# W023.net
KiCad netlist of a schematic drawn in EAGLE
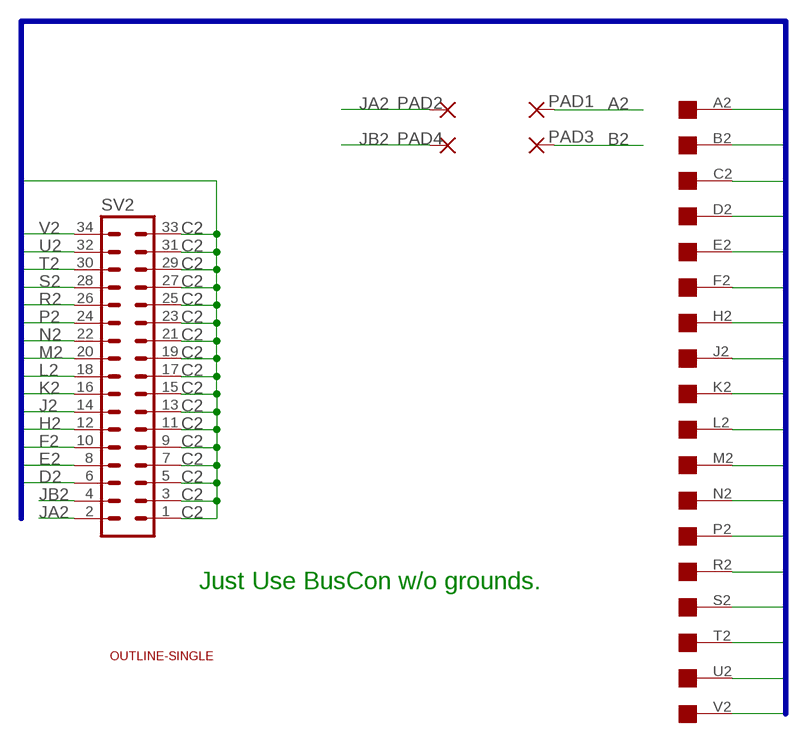
[diagram p0: schematic, sheet 1]

(export (version "E")
  (design (tool "Eeschema 10.0.6"))
  (components
    (comp (ref "PAD1")
      (value "1,6/0,8")
      (footprint "eagle-import:1,6_0,8")
      (libsource (lib "eagle-import") (part "1,6/0,8"))
    )
    (comp (ref "PAD2")
      (value "1,6/0,8")
      (footprint "eagle-import:1,6_0,8")
      (libsource (lib "eagle-import") (part "1,6/0,8"))
    )
    (comp (ref "PAD3")
      (value "1,6/0,8")
      (footprint "eagle-import:1,6_0,8")
      (libsource (lib "eagle-import") (part "1,6/0,8"))
    )
    (comp (ref "PAD4")
      (value "1,6/0,8")
      (footprint "eagle-import:1,6_0,8")
      (libsource (lib "eagle-import") (part "1,6/0,8"))
    )
    (comp (ref "SV2")
      (value "MA17-2")
      (footprint "eagle-import:MA17-2")
      (libsource (lib "eagle-import") (part "MA17-2"))
    )
    (comp (ref "U$1")
      (value "EDGE-1")
      (footprint "eagle-import:EDGE-CON1")
      (libsource (lib "eagle-import") (part "EDGE-1"))
    )
    (comp (ref "U$2")
      (value "OUTLINE-SINGLE")
      (footprint "eagle-import:SINGLE")
      (libsource (lib "eagle-import") (part "OUTLINE-SINGLE"))
    )
  )
  (nets
    (net (code "1") (name "/A2") (class "Default")
      (node (ref "PAD1") (pin "1") (pinfunction "P_1") (pintype "passive"))
      (node (ref "U$1") (pin "A2") (pinfunction "1_A2") (pintype "bidirectional"))
    )
    (net (code "2") (name "/B2") (class "Default")
      (node (ref "PAD3") (pin "1") (pinfunction "P_1") (pintype "passive"))
      (node (ref "U$1") (pin "B2") (pinfunction "1_B2") (pintype "bidirectional"))
    )
    (net (code "3") (name "/C2") (class "Default")
      (node (ref "SV2") (pin "1") (pinfunction "1_1") (pintype "passive"))
      (node (ref "SV2") (pin "11") (pinfunction "11_11") (pintype "passive"))
      (node (ref "SV2") (pin "13") (pinfunction "13_13") (pintype "passive"))
      (node (ref "SV2") (pin "15") (pinfunction "15_15") (pintype "passive"))
      (node (ref "SV2") (pin "17") (pinfunction "17_17") (pintype "passive"))
      (node (ref "SV2") (pin "19") (pinfunction "19_19") (pintype "passive"))
      (node (ref "SV2") (pin "21") (pinfunction "21_21") (pintype "passive"))
      (node (ref "SV2") (pin "23") (pinfunction "23_23") (pintype "passive"))
      (node (ref "SV2") (pin "25") (pinfunction "25_25") (pintype "passive"))
      (node (ref "SV2") (pin "27") (pinfunction "27_27") (pintype "passive"))
      (node (ref "SV2") (pin "29") (pinfunction "29_29") (pintype "passive"))
      (node (ref "SV2") (pin "3") (pinfunction "3_3") (pintype "passive"))
      (node (ref "SV2") (pin "31") (pinfunction "31_31") (pintype "passive"))
      (node (ref "SV2") (pin "33") (pinfunction "33_33") (pintype "passive"))
      (node (ref "SV2") (pin "5") (pinfunction "5_5") (pintype "passive"))
      (node (ref "SV2") (pin "7") (pinfunction "7_7") (pintype "passive"))
      (node (ref "SV2") (pin "9") (pinfunction "9_9") (pintype "passive"))
      (node (ref "U$1") (pin "C2") (pinfunction "1_C2") (pintype "bidirectional"))
    )
    (net (code "4") (name "/D2") (class "Default")
      (node (ref "SV2") (pin "6") (pinfunction "6_6") (pintype "passive"))
      (node (ref "U$1") (pin "D2") (pinfunction "1_D2") (pintype "bidirectional"))
    )
    (net (code "5") (name "/E2") (class "Default")
      (node (ref "SV2") (pin "8") (pinfunction "8_8") (pintype "passive"))
      (node (ref "U$1") (pin "E2") (pinfunction "1_E2") (pintype "bidirectional"))
    )
    (net (code "6") (name "/F2") (class "Default")
      (node (ref "SV2") (pin "10") (pinfunction "10_10") (pintype "passive"))
      (node (ref "U$1") (pin "F2") (pinfunction "1_F2") (pintype "bidirectional"))
    )
    (net (code "7") (name "/H2") (class "Default")
      (node (ref "SV2") (pin "12") (pinfunction "12_12") (pintype "passive"))
      (node (ref "U$1") (pin "H2") (pinfunction "1_H2") (pintype "bidirectional"))
    )
    (net (code "8") (name "/J2") (class "Default")
      (node (ref "SV2") (pin "14") (pinfunction "14_14") (pintype "passive"))
      (node (ref "U$1") (pin "J2") (pinfunction "1_J2") (pintype "bidirectional"))
    )
    (net (code "9") (name "/JA2") (class "Default")
      (node (ref "PAD2") (pin "1") (pinfunction "P_1") (pintype "passive"))
      (node (ref "SV2") (pin "2") (pinfunction "2_2") (pintype "passive"))
    )
    (net (code "10") (name "/JB2") (class "Default")
      (node (ref "PAD4") (pin "1") (pinfunction "P_1") (pintype "passive"))
      (node (ref "SV2") (pin "4") (pinfunction "4_4") (pintype "passive"))
    )
    (net (code "11") (name "/K2") (class "Default")
      (node (ref "SV2") (pin "16") (pinfunction "16_16") (pintype "passive"))
      (node (ref "U$1") (pin "K2") (pinfunction "1_K2") (pintype "bidirectional"))
    )
    (net (code "12") (name "/L2") (class "Default")
      (node (ref "SV2") (pin "18") (pinfunction "18_18") (pintype "passive"))
      (node (ref "U$1") (pin "L2") (pinfunction "1_L2") (pintype "bidirectional"))
    )
    (net (code "13") (name "/M2") (class "Default")
      (node (ref "SV2") (pin "20") (pinfunction "20_20") (pintype "passive"))
      (node (ref "U$1") (pin "M2") (pinfunction "1_M2") (pintype "bidirectional"))
    )
    (net (code "14") (name "/N2") (class "Default")
      (node (ref "SV2") (pin "22") (pinfunction "22_22") (pintype "passive"))
      (node (ref "U$1") (pin "N2") (pinfunction "1_N2") (pintype "bidirectional"))
    )
    (net (code "15") (name "/P2") (class "Default")
      (node (ref "SV2") (pin "24") (pinfunction "24_24") (pintype "passive"))
      (node (ref "U$1") (pin "P2") (pinfunction "1_P2") (pintype "bidirectional"))
    )
    (net (code "16") (name "/R2") (class "Default")
      (node (ref "SV2") (pin "26") (pinfunction "26_26") (pintype "passive"))
      (node (ref "U$1") (pin "R2") (pinfunction "1_R2") (pintype "bidirectional"))
    )
    (net (code "17") (name "/S2") (class "Default")
      (node (ref "SV2") (pin "28") (pinfunction "28_28") (pintype "passive"))
      (node (ref "U$1") (pin "S2") (pinfunction "1_S2") (pintype "bidirectional"))
    )
    (net (code "18") (name "/T2") (class "Default")
      (node (ref "SV2") (pin "30") (pinfunction "30_30") (pintype "passive"))
      (node (ref "U$1") (pin "T2") (pinfunction "1_T2") (pintype "bidirectional"))
    )
    (net (code "19") (name "/U2") (class "Default")
      (node (ref "SV2") (pin "32") (pinfunction "32_32") (pintype "passive"))
      (node (ref "U$1") (pin "U2") (pinfunction "1_U2") (pintype "bidirectional"))
    )
    (net (code "20") (name "/V2") (class "Default")
      (node (ref "SV2") (pin "34") (pinfunction "34_34") (pintype "passive"))
      (node (ref "U$1") (pin "V2") (pinfunction "1_V2") (pintype "bidirectional"))
    )
  )
)
